# SkyKontrol-powerMeter.net
KiCad netlist of a schematic drawn in EAGLE
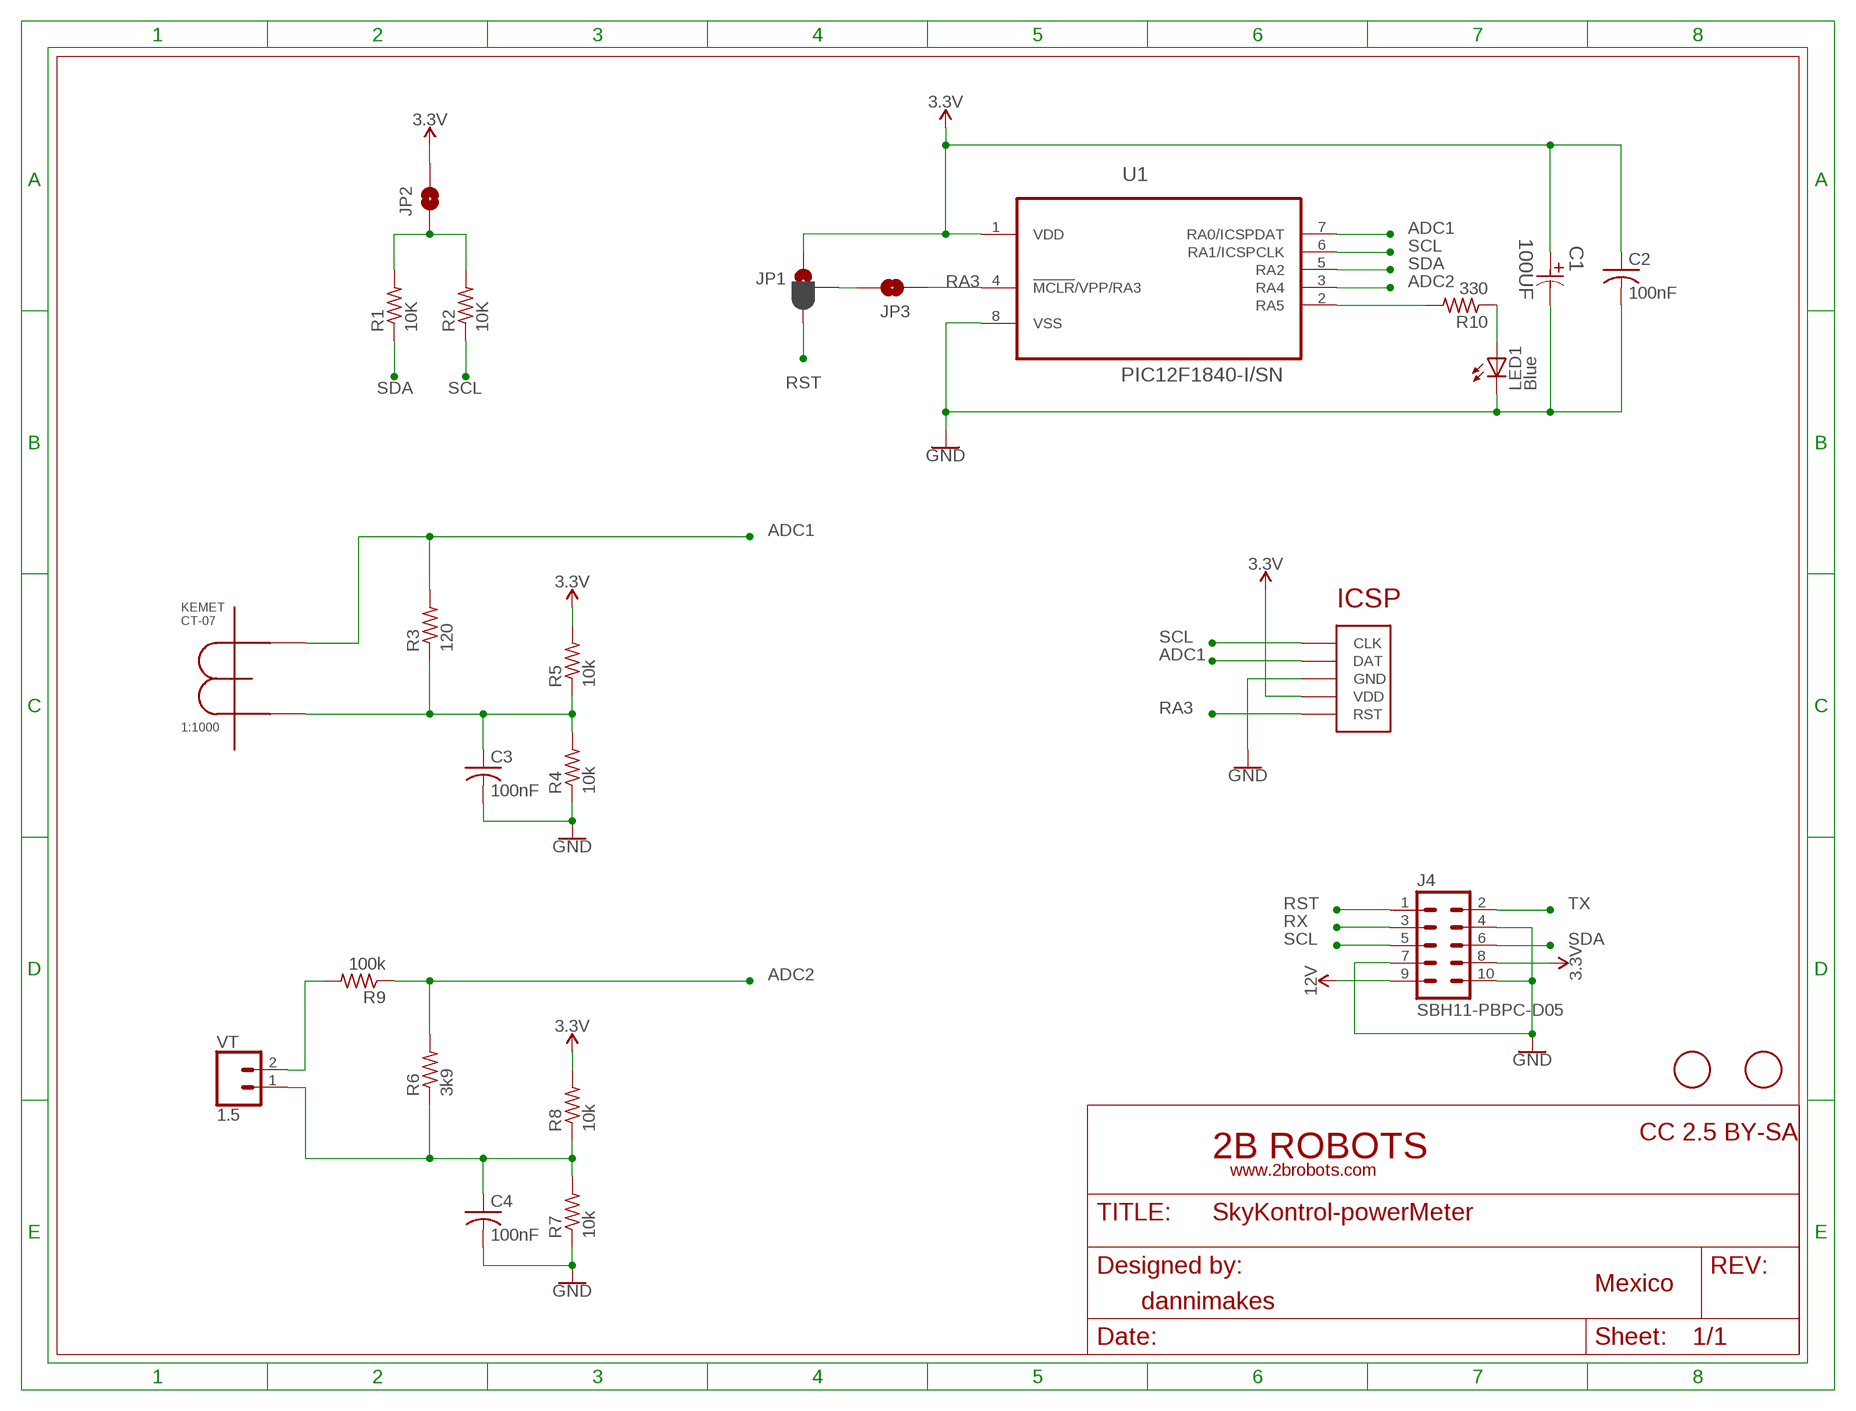
[diagram p0: schematic, sheet 1]

(export (version "E")
  (design (tool "Eeschema 10.0.6"))
  (components
    (comp (ref "C1")
      (value "100UF")
      (footprint "eagle-import:CAPAE660X800N")
      (fields (field (name "MPN") "EEE-HA1E101XP") (field (name "TOLERANCE") "±20 %"))
      (libsource (lib "eagle-import") (part "EEE--CASE-D8HA1E101XP"))
    )
    (comp (ref "C2")
      (value "100nF")
      (footprint "eagle-import:C0603K")
      (libsource (lib "eagle-import") (part "C-USC0603K"))
    )
    (comp (ref "C3")
      (value "100nF")
      (footprint "eagle-import:C0603K")
      (libsource (lib "eagle-import") (part "C-USC0603K"))
    )
    (comp (ref "C4")
      (value "100nF")
      (footprint "eagle-import:C0603K")
      (libsource (lib "eagle-import") (part "C-USC0603K"))
    )
    (comp (ref "J4")
      (value "SBH11-PBPC-D05")
      (footprint "eagle-import:SBH11-PBPC-D05")
      (libsource (lib "eagle-import") (part "SBH11-PBPC-D05"))
    )
    (comp (ref "JP1")
      (value "JUMPER-SMT_3_1-NC_PASTE_SILK")
      (footprint "eagle-import:SMT-JUMPER_3_1-NC_PASTE_SILK")
      (libsource (lib "eagle-import") (part "JUMPER-SMT_3_1-NC_PASTE_SILK"))
    )
    (comp (ref "JP2")
      (value "JUMPER-SMT_2_NO_SILK")
      (footprint "eagle-import:SMT-JUMPER_2_NO_SILK")
      (libsource (lib "eagle-import") (part "JUMPER-SMT_2_NO_SILK"))
    )
    (comp (ref "JP3")
      (value "JUMPER-SMT_2_NO_SILK")
      (footprint "eagle-import:SMT-JUMPER_2_NO_SILK")
      (libsource (lib "eagle-import") (part "JUMPER-SMT_2_NO_SILK"))
    )
    (comp (ref "LED1")
      (value "Blue")
      (footprint "eagle-import:CHIPLED_1206")
      (libsource (lib "eagle-import") (part "LEDCHIPLED_1206"))
    )
    (comp (ref "R1")
      (value "10K")
      (footprint "eagle-import:R0805")
      (libsource (lib "eagle-import") (part "R-US_R0805"))
    )
    (comp (ref "R2")
      (value "10K")
      (footprint "eagle-import:R0805")
      (libsource (lib "eagle-import") (part "R-US_R0805"))
    )
    (comp (ref "R3")
      (value "120")
      (footprint "eagle-import:R0805")
      (libsource (lib "eagle-import") (part "R-US_R0805"))
    )
    (comp (ref "R4")
      (value "10k")
      (footprint "eagle-import:R0805")
      (libsource (lib "eagle-import") (part "R-US_R0805"))
    )
    (comp (ref "R5")
      (value "10k")
      (footprint "eagle-import:R0805")
      (libsource (lib "eagle-import") (part "R-US_R0805"))
    )
    (comp (ref "R6")
      (value "3k9")
      (footprint "eagle-import:R0805")
      (libsource (lib "eagle-import") (part "R-US_R0805"))
    )
    (comp (ref "R7")
      (value "10k")
      (footprint "eagle-import:R0805")
      (libsource (lib "eagle-import") (part "R-US_R0805"))
    )
    (comp (ref "R8")
      (value "10k")
      (footprint "eagle-import:R0805")
      (libsource (lib "eagle-import") (part "R-US_R0805"))
    )
    (comp (ref "R9")
      (value "100k")
      (footprint "eagle-import:R0805")
      (libsource (lib "eagle-import") (part "R-US_R0805"))
    )
    (comp (ref "R10")
      (value "330")
      (footprint "eagle-import:R0805")
      (libsource (lib "eagle-import") (part "R-US_R0805"))
    )
    (comp (ref "U$1")
      (value "FIDUCIAL")
      (footprint "eagle-import:FIDUCIAL_1MM")
      (libsource (lib "eagle-import") (part "FIDUCIAL"))
    )
    (comp (ref "U$2")
      (value "ICSP_POGO")
      (footprint "eagle-import:ICSP_POGO")
      (libsource (lib "eagle-import") (part "ICSP_POGO"))
    )
    (comp (ref "U$3")
      (value "FIDUCIAL")
      (footprint "eagle-import:FIDUCIAL_1MM")
      (libsource (lib "eagle-import") (part "FIDUCIAL"))
    )
    (comp (ref "U$4")
      (value "CT-07KEMET")
      (footprint "eagle-import:CT-07")
      (libsource (lib "eagle-import") (part "CT-07KEMET"))
    )
    (comp (ref "U1")
      (value "PIC12F1840-I/SN")
      (footprint "eagle-import:SOIC127P600X175-8N")
      (libsource (lib "eagle-import") (part "PIC12F1840-I/SN"))
    )
    (comp (ref "VT")
      (value "1.5")
      (footprint "eagle-import:SCREWTERMINAL-5MM-2")
      (libsource (lib "eagle-import") (part "CONN_025MM"))
    )
  )
  (nets
    (net (code "1") (name "/ADC1") (class "Default")
      (node (ref "R3") (pin "2") (pinfunction "2_2") (pintype "passive"))
      (node (ref "U$2") (pin "P$4") (pinfunction "DAT_P$4") (pintype "bidirectional"))
      (node (ref "U$4") (pin "P$1") (pinfunction "C1_P$1") (pintype "bidirectional"))
      (node (ref "U1") (pin "7") (pinfunction "RA0/ICSPDAT_7") (pintype "bidirectional"))
    )
    (net (code "2") (name "/ADC2") (class "Default")
      (node (ref "R6") (pin "2") (pinfunction "2_2") (pintype "passive"))
      (node (ref "R9") (pin "1") (pinfunction "1_1") (pintype "passive"))
      (node (ref "U1") (pin "3") (pinfunction "RA4_3") (pintype "bidirectional"))
    )
    (net (code "3") (name "/RA3") (class "Default")
      (node (ref "JP3") (pin "1") (pinfunction "1_1") (pintype "passive"))
      (node (ref "U$2") (pin "P$1") (pinfunction "RST_P$1") (pintype "bidirectional"))
      (node (ref "U1") (pin "4") (pinfunction "~{MCLR}/VPP/RA3_4") (pintype "input"))
    )
    (net (code "4") (name "/RST") (class "Default")
      (node (ref "J4") (pin "1") (pinfunction "1_1") (pintype "passive"))
      (node (ref "JP1") (pin "3") (pinfunction "3_3") (pintype "passive"))
    )
    (net (code "5") (name "/RX") (class "Default")
      (node (ref "J4") (pin "3") (pinfunction "3_3") (pintype "passive"))
    )
    (net (code "6") (name "/SCL") (class "Default")
      (node (ref "J4") (pin "5") (pinfunction "5_5") (pintype "passive"))
      (node (ref "R2") (pin "1") (pinfunction "1_1") (pintype "passive"))
      (node (ref "U$2") (pin "P$5") (pinfunction "CLK_P$5") (pintype "bidirectional"))
      (node (ref "U1") (pin "6") (pinfunction "RA1/ICSPCLK_6") (pintype "bidirectional"))
    )
    (net (code "7") (name "/SDA") (class "Default")
      (node (ref "J4") (pin "6") (pinfunction "6_6") (pintype "passive"))
      (node (ref "R1") (pin "1") (pinfunction "1_1") (pintype "passive"))
      (node (ref "U1") (pin "5") (pinfunction "RA2_5") (pintype "bidirectional"))
    )
    (net (code "8") (name "/TX") (class "Default")
      (node (ref "J4") (pin "2") (pinfunction "2_2") (pintype "passive"))
    )
    (net (code "9") (name "3.3V") (class "Default")
      (node (ref "C1") (pin "1") (pinfunction "1_1") (pintype "passive"))
      (node (ref "C2") (pin "1") (pinfunction "1_1") (pintype "passive"))
      (node (ref "J4") (pin "8") (pinfunction "8_8") (pintype "passive"))
      (node (ref "JP1") (pin "1") (pinfunction "1_1") (pintype "passive"))
      (node (ref "JP2") (pin "2") (pinfunction "2_2") (pintype "passive"))
      (node (ref "R5") (pin "2") (pinfunction "2_2") (pintype "passive"))
      (node (ref "R8") (pin "2") (pinfunction "2_2") (pintype "passive"))
      (node (ref "U$2") (pin "P$2") (pinfunction "VDD_P$2") (pintype "bidirectional"))
      (node (ref "U1") (pin "1") (pinfunction "VDD_1") (pintype "power_in"))
    )
    (net (code "10") (name "12V") (class "Default")
      (node (ref "J4") (pin "9") (pinfunction "9_9") (pintype "passive"))
    )
    (net (code "11") (name "GND") (class "Default")
      (node (ref "C1") (pin "2") (pinfunction "2_2") (pintype "passive"))
      (node (ref "C2") (pin "2") (pinfunction "2_2") (pintype "passive"))
      (node (ref "C3") (pin "2") (pinfunction "2_2") (pintype "passive"))
      (node (ref "C4") (pin "2") (pinfunction "2_2") (pintype "passive"))
      (node (ref "J4") (pin "10") (pinfunction "10_10") (pintype "passive"))
      (node (ref "J4") (pin "4") (pinfunction "4_4") (pintype "passive"))
      (node (ref "J4") (pin "7") (pinfunction "7_7") (pintype "passive"))
      (node (ref "LED1") (pin "C") (pinfunction "C_C") (pintype "passive"))
      (node (ref "R4") (pin "1") (pinfunction "1_1") (pintype "passive"))
      (node (ref "R7") (pin "1") (pinfunction "1_1") (pintype "passive"))
      (node (ref "U$2") (pin "P$3") (pinfunction "GND_P$3") (pintype "bidirectional"))
      (node (ref "U1") (pin "8") (pinfunction "VSS_8") (pintype "power_in"))
    )
    (net (code "12") (name "Net-(C4-Pad1)") (class "Default")
      (node (ref "C4") (pin "1") (pinfunction "1_1") (pintype "passive"))
      (node (ref "R6") (pin "1") (pinfunction "1_1") (pintype "passive"))
      (node (ref "R7") (pin "2") (pinfunction "2_2") (pintype "passive"))
      (node (ref "R8") (pin "1") (pinfunction "1_1") (pintype "passive"))
      (node (ref "VT") (pin "1") (pinfunction "1_1") (pintype "passive"))
    )
    (net (code "13") (name "Net-(JP1-Pad2)") (class "Default")
      (node (ref "JP1") (pin "2") (pinfunction "2_2") (pintype "passive"))
      (node (ref "JP3") (pin "2") (pinfunction "2_2") (pintype "passive"))
    )
    (net (code "14") (name "Net-(JP2-Pad1)") (class "Default")
      (node (ref "JP2") (pin "1") (pinfunction "1_1") (pintype "passive"))
      (node (ref "R1") (pin "2") (pinfunction "2_2") (pintype "passive"))
      (node (ref "R2") (pin "2") (pinfunction "2_2") (pintype "passive"))
    )
    (net (code "15") (name "Net-(LED1-PadA)") (class "Default")
      (node (ref "LED1") (pin "A") (pinfunction "A_A") (pintype "passive"))
      (node (ref "R10") (pin "1") (pinfunction "1_1") (pintype "passive"))
    )
    (net (code "16") (name "Net-(R9-Pad2)") (class "Default")
      (node (ref "R9") (pin "2") (pinfunction "2_2") (pintype "passive"))
      (node (ref "VT") (pin "2") (pinfunction "2_2") (pintype "passive"))
    )
    (net (code "17") (name "Net-(U$4-C2)") (class "Default")
      (node (ref "C3") (pin "1") (pinfunction "1_1") (pintype "passive"))
      (node (ref "R3") (pin "1") (pinfunction "1_1") (pintype "passive"))
      (node (ref "R4") (pin "2") (pinfunction "2_2") (pintype "passive"))
      (node (ref "R5") (pin "1") (pinfunction "1_1") (pintype "passive"))
      (node (ref "U$4") (pin "P$2") (pinfunction "C2_P$2") (pintype "bidirectional"))
    )
    (net (code "18") (name "Net-(U1-RA5)") (class "Default")
      (node (ref "R10") (pin "2") (pinfunction "2_2") (pintype "passive"))
      (node (ref "U1") (pin "2") (pinfunction "RA5_2") (pintype "bidirectional"))
    )
  )
)
